# XMOS_power.net
KiCad netlist of a schematic drawn in Altium Designer
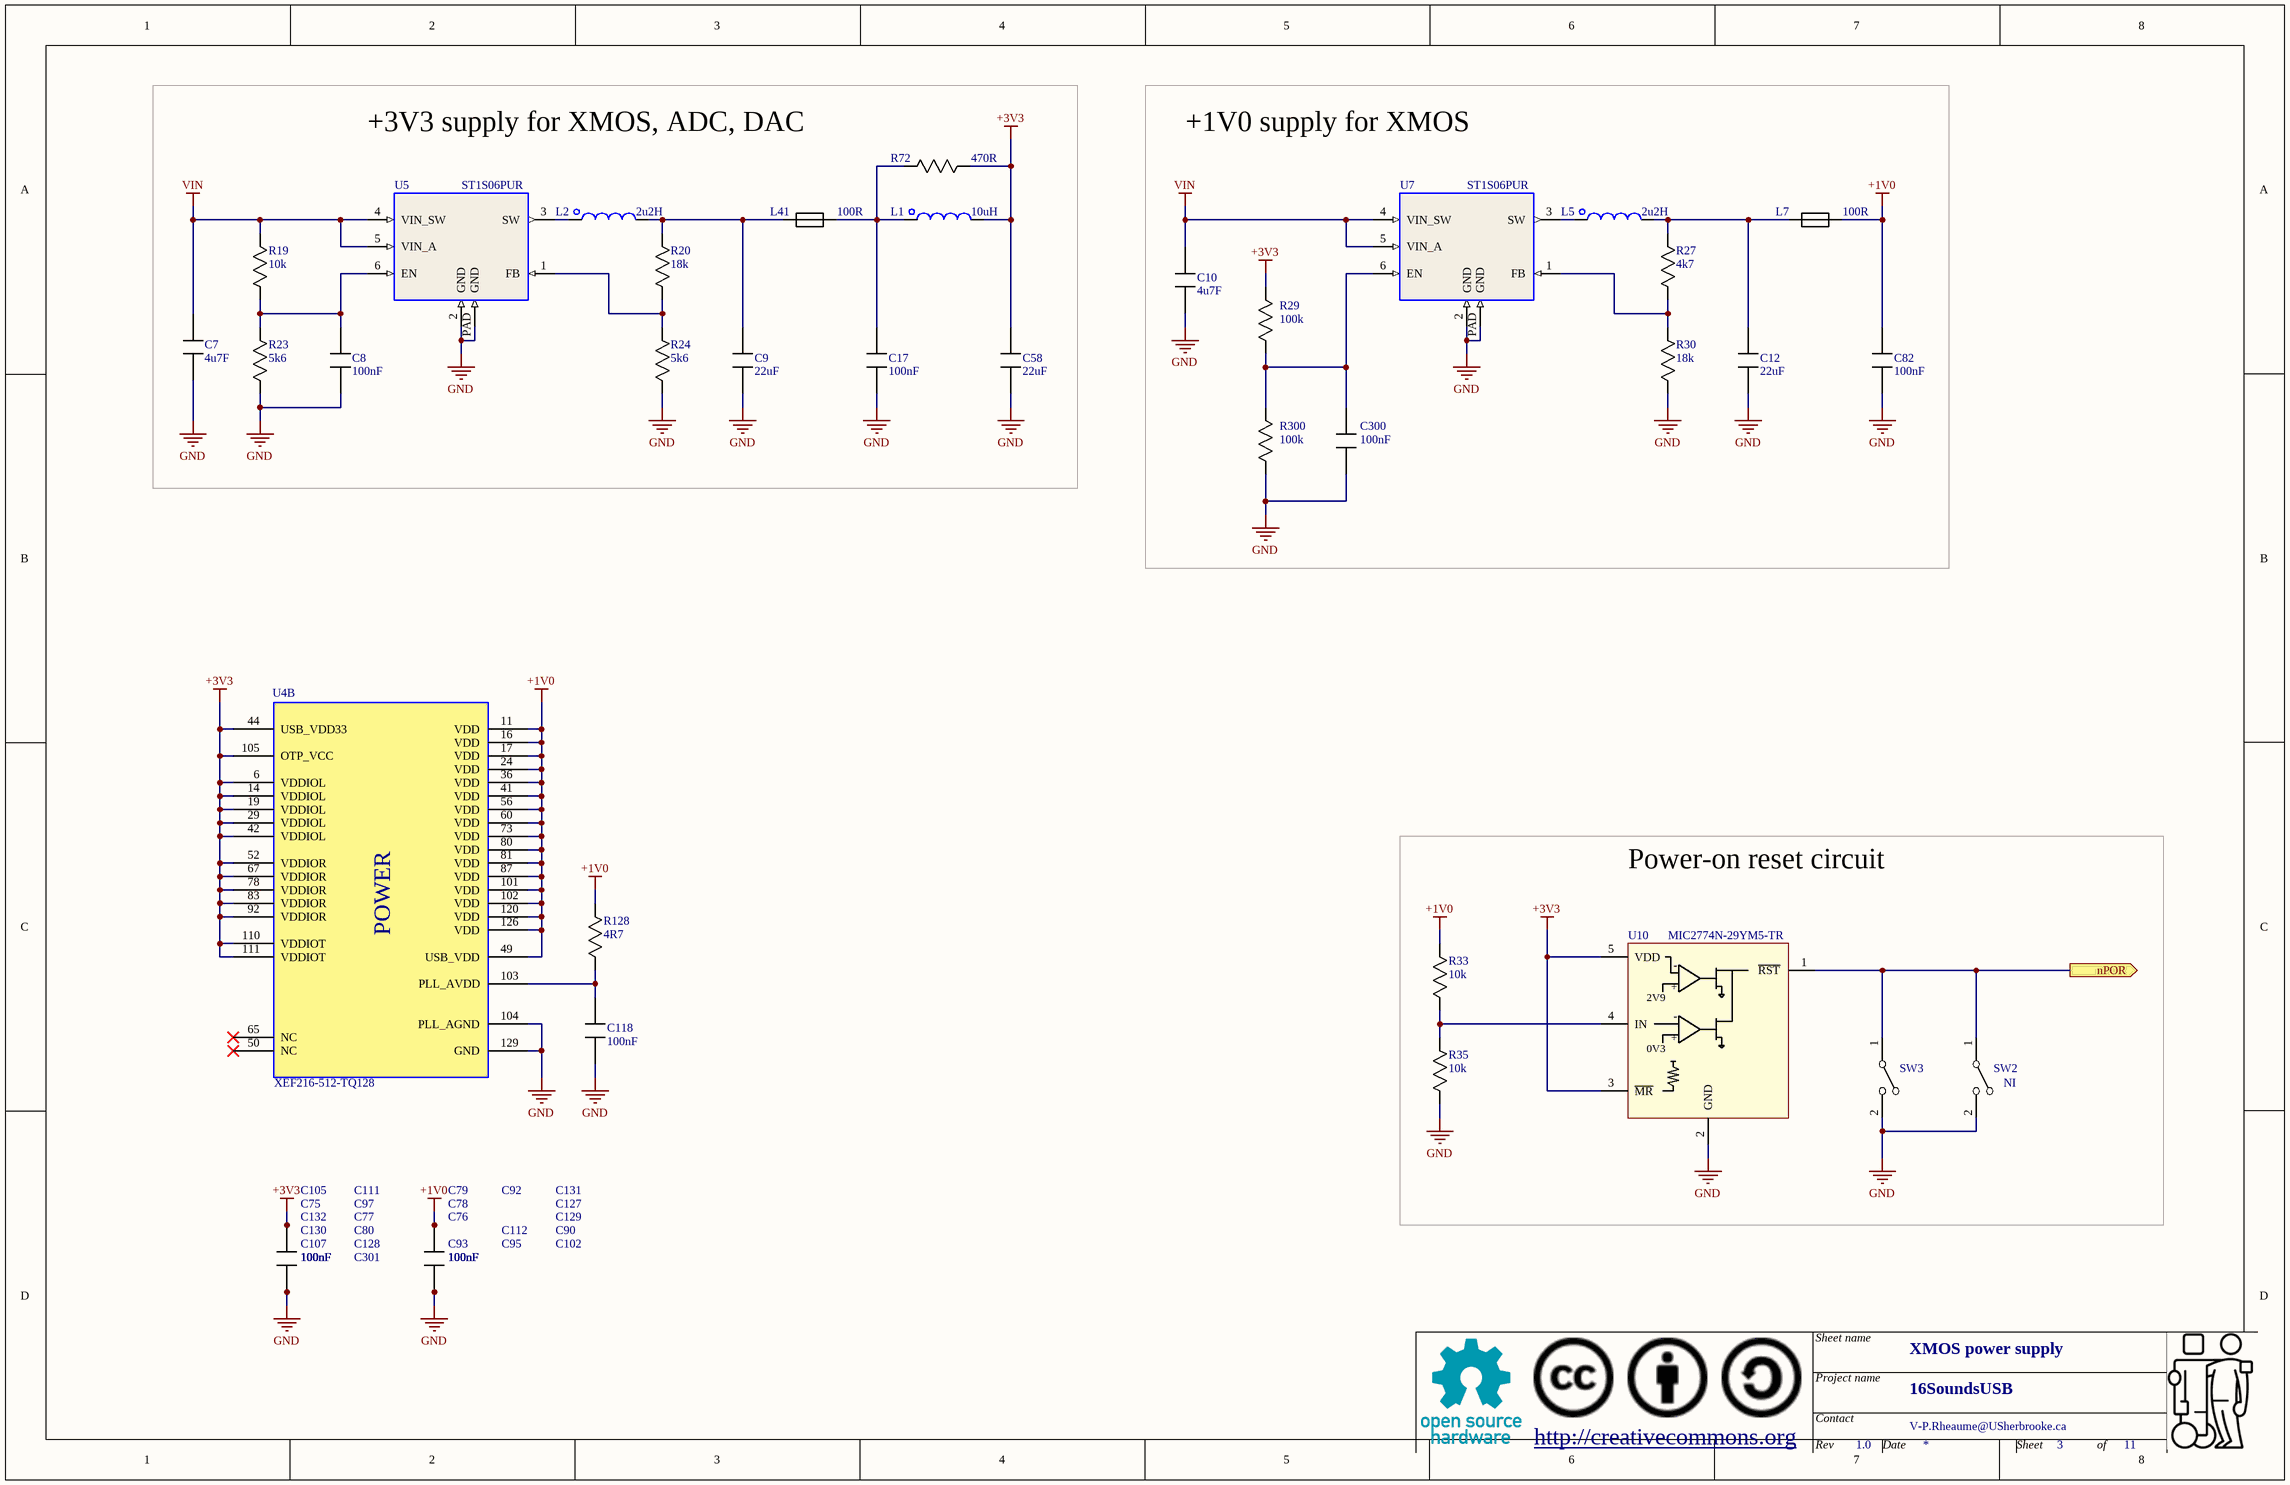
[diagram p0: XMOS_power.SchDoc]

(export (version "E")
  (design (tool "Eeschema 10.0.6"))
  (components
    (comp (ref "C7")
      (value "4u7F")
      (footprint "0805")
      (description "Capacitor")
      (fields (field (name "MFG") "Samsung"))
      (libsource (lib "INTER_2014") (part "Capacitor"))
    )
    (comp (ref "C8")
      (value "100nF")
      (footprint "0603")
      (description "Capacitor")
      (fields (field (name "MFG") "Samsung"))
      (libsource (lib "INTER_2014") (part "Capacitor"))
    )
    (comp (ref "C9")
      (value "22uF")
      (footprint "1206")
      (description "Capacitor")
      (fields (field (name "MFG") "Samsung"))
      (libsource (lib "INTER_2014") (part "Capacitor"))
    )
    (comp (ref "C10")
      (value "4u7F")
      (footprint "0805")
      (description "Capacitor")
      (fields (field (name "MFG") "Samsung"))
      (libsource (lib "INTER_2014") (part "Capacitor"))
    )
    (comp (ref "C12")
      (value "22uF")
      (footprint "1206")
      (description "Capacitor")
      (fields (field (name "MFG") "Samsung"))
      (libsource (lib "INTER_2014") (part "Capacitor"))
    )
    (comp (ref "C17")
      (value "100nF")
      (footprint "0603")
      (description "Capacitor")
      (fields (field (name "MFG") "Samsung"))
      (libsource (lib "INTER_2014") (part "Capacitor"))
    )
    (comp (ref "C58")
      (value "22uF")
      (footprint "1206")
      (description "Capacitor")
      (fields (field (name "MFG") "Samsung"))
      (libsource (lib "INTER_2014") (part "Capacitor"))
    )
    (comp (ref "C75")
      (value "100nF")
      (footprint "0603")
      (description "Capacitor")
      (fields (field (name "MFG") "Samsung"))
      (libsource (lib "INTER_2014") (part "Capacitor"))
    )
    (comp (ref "C76")
      (value "100nF")
      (footprint "0603")
      (description "Capacitor")
      (fields (field (name "MFG") "Samsung"))
      (libsource (lib "INTER_2014") (part "Capacitor"))
    )
    (comp (ref "C77")
      (value "100nF")
      (footprint "0603")
      (description "Capacitor")
      (fields (field (name "MFG") "Samsung"))
      (libsource (lib "INTER_2014") (part "Capacitor"))
    )
    (comp (ref "C78")
      (value "100nF")
      (footprint "0603")
      (description "Capacitor")
      (fields (field (name "MFG") "Samsung"))
      (libsource (lib "INTER_2014") (part "Capacitor"))
    )
    (comp (ref "C79")
      (value "100nF")
      (footprint "0603")
      (description "Capacitor")
      (fields (field (name "MFG") "Samsung"))
      (libsource (lib "INTER_2014") (part "Capacitor"))
    )
    (comp (ref "C80")
      (value "100nF")
      (footprint "0603")
      (description "Capacitor")
      (fields (field (name "MFG") "Samsung"))
      (libsource (lib "INTER_2014") (part "Capacitor"))
    )
    (comp (ref "C82")
      (value "100nF")
      (footprint "0603")
      (description "Capacitor")
      (fields (field (name "MFG") "Samsung"))
      (libsource (lib "INTER_2014") (part "Capacitor"))
    )
    (comp (ref "C90")
      (value "100nF")
      (footprint "0603")
      (description "Capacitor")
      (fields (field (name "MFG") "Samsung"))
      (libsource (lib "INTER_2014") (part "Capacitor"))
    )
    (comp (ref "C92")
      (value "100nF")
      (footprint "0603")
      (description "Capacitor")
      (fields (field (name "MFG") "Samsung"))
      (libsource (lib "INTER_2014") (part "Capacitor"))
    )
    (comp (ref "C93")
      (value "100nF")
      (footprint "0603")
      (description "Capacitor")
      (fields (field (name "MFG") "Samsung"))
      (libsource (lib "INTER_2014") (part "Capacitor"))
    )
    (comp (ref "C95")
      (value "100nF")
      (footprint "0603")
      (description "Capacitor")
      (fields (field (name "MFG") "Samsung"))
      (libsource (lib "INTER_2014") (part "Capacitor"))
    )
    (comp (ref "C97")
      (value "100nF")
      (footprint "0603")
      (description "Capacitor")
      (fields (field (name "MFG") "Samsung"))
      (libsource (lib "INTER_2014") (part "Capacitor"))
    )
    (comp (ref "C102")
      (value "100nF")
      (footprint "0603")
      (description "Capacitor")
      (fields (field (name "MFG") "Samsung"))
      (libsource (lib "INTER_2014") (part "Capacitor"))
    )
    (comp (ref "C105")
      (value "100nF")
      (footprint "0603")
      (description "Capacitor")
      (fields (field (name "MFG") "Samsung"))
      (libsource (lib "INTER_2014") (part "Capacitor"))
    )
    (comp (ref "C107")
      (value "100nF")
      (footprint "0603")
      (description "Capacitor")
      (fields (field (name "MFG") "Samsung"))
      (libsource (lib "INTER_2014") (part "Capacitor"))
    )
    (comp (ref "C111")
      (value "100nF")
      (footprint "0603")
      (description "Capacitor")
      (fields (field (name "MFG") "Samsung"))
      (libsource (lib "INTER_2014") (part "Capacitor"))
    )
    (comp (ref "C112")
      (value "100nF")
      (footprint "0603")
      (description "Capacitor")
      (fields (field (name "MFG") "Samsung"))
      (libsource (lib "INTER_2014") (part "Capacitor"))
    )
    (comp (ref "C118")
      (value "100nF")
      (footprint "0603")
      (description "Capacitor")
      (fields (field (name "MFG") "Samsung"))
      (libsource (lib "INTER_2014") (part "Capacitor"))
    )
    (comp (ref "C127")
      (value "100nF")
      (footprint "0603")
      (description "Capacitor")
      (fields (field (name "MFG") "Samsung"))
      (libsource (lib "INTER_2014") (part "Capacitor"))
    )
    (comp (ref "C128")
      (value "100nF")
      (footprint "0603")
      (description "Capacitor")
      (fields (field (name "MFG") "Samsung"))
      (libsource (lib "INTER_2014") (part "Capacitor"))
    )
    (comp (ref "C129")
      (value "100nF")
      (footprint "0603")
      (description "Capacitor")
      (fields (field (name "MFG") "Samsung"))
      (libsource (lib "INTER_2014") (part "Capacitor"))
    )
    (comp (ref "C130")
      (value "100nF")
      (footprint "0603")
      (description "Capacitor")
      (fields (field (name "MFG") "Samsung"))
      (libsource (lib "INTER_2014") (part "Capacitor"))
    )
    (comp (ref "C131")
      (value "100nF")
      (footprint "0603")
      (description "Capacitor")
      (fields (field (name "MFG") "Samsung"))
      (libsource (lib "INTER_2014") (part "Capacitor"))
    )
    (comp (ref "C132")
      (value "100nF")
      (footprint "0603")
      (description "Capacitor")
      (fields (field (name "MFG") "Samsung"))
      (libsource (lib "INTER_2014") (part "Capacitor"))
    )
    (comp (ref "C300")
      (value "100nF")
      (footprint "0603")
      (description "Capacitor")
      (fields (field (name "MFG") "Samsung"))
      (libsource (lib "INTER_2014") (part "Capacitor"))
    )
    (comp (ref "C301")
      (value "100nF")
      (footprint "0603")
      (description "Capacitor")
      (fields (field (name "MFG") "Samsung"))
      (libsource (lib "INTER_2014") (part "Capacitor"))
    )
    (comp (ref "L1")
      (value "10uH")
      (footprint "IND_252012CDMC/DS")
      (description "Inductor")
      (fields (field (name "MFG") "Murata"))
      (libsource (lib "INTER_2014") (part "Inductor"))
    )
    (comp (ref "L2")
      (value "2u2H")
      (footprint "IND_252012CDMC/DS")
      (description "Inductor")
      (fields (field (name "MFG") "Murata"))
      (libsource (lib "INTER_2014") (part "Inductor"))
    )
    (comp (ref "L5")
      (value "2u2H")
      (footprint "IND_252012CDMC/DS")
      (description "Inductor")
      (fields (field (name "MFG") "Murata"))
      (libsource (lib "INTER_2014") (part "Inductor"))
    )
    (comp (ref "L7")
      (value "100R")
      (footprint "0805")
      (description "Ferrite")
      (fields (field (name "MFG") "Bourns"))
      (libsource (lib "INTER_2014") (part "Ferrite"))
    )
    (comp (ref "L41")
      (value "100R")
      (footprint "0805")
      (description "Ferrite")
      (fields (field (name "MFG") "Bourns"))
      (libsource (lib "INTER_2014") (part "Ferrite"))
    )
    (comp (ref "R19")
      (value "10k")
      (footprint "0603")
      (description "Resistor")
      (fields (field (name "MFG") "Yageo"))
      (libsource (lib "INTER_2014") (part "Resistor"))
    )
    (comp (ref "R20")
      (value "18k")
      (footprint "0603")
      (description "Resistor")
      (fields (field (name "MFG") "Yageo"))
      (libsource (lib "INTER_2014") (part "Resistor"))
    )
    (comp (ref "R23")
      (value "5k6")
      (footprint "0603")
      (description "Resistor")
      (fields (field (name "MFG") "Yageo"))
      (libsource (lib "INTER_2014") (part "Resistor"))
    )
    (comp (ref "R24")
      (value "5k6")
      (footprint "0603")
      (description "Resistor")
      (fields (field (name "MFG") "Yageo"))
      (libsource (lib "INTER_2014") (part "Resistor"))
    )
    (comp (ref "R27")
      (value "4k7")
      (footprint "0603")
      (description "Resistor")
      (fields (field (name "MFG") "Yageo"))
      (libsource (lib "INTER_2014") (part "Resistor"))
    )
    (comp (ref "R29")
      (value "100k")
      (footprint "0603")
      (description "Resistor")
      (fields (field (name "MFG") "Yageo"))
      (libsource (lib "INTER_2014") (part "Resistor"))
    )
    (comp (ref "R30")
      (value "18k")
      (footprint "0603")
      (description "Resistor")
      (fields (field (name "MFG") "Yageo"))
      (libsource (lib "INTER_2014") (part "Resistor"))
    )
    (comp (ref "R33")
      (value "10k")
      (footprint "0603")
      (description "Resistor")
      (fields (field (name "MFG") "Yageo"))
      (libsource (lib "INTER_2014") (part "Resistor"))
    )
    (comp (ref "R35")
      (value "10k")
      (footprint "0603")
      (description "Resistor")
      (fields (field (name "MFG") "Yageo"))
      (libsource (lib "INTER_2014") (part "Resistor"))
    )
    (comp (ref "R72")
      (value "470R")
      (footprint "0603")
      (description "Resistor")
      (fields (field (name "MFG") "Yageo"))
      (libsource (lib "INTER_2014") (part "Resistor"))
    )
    (comp (ref "R128")
      (value "4R7")
      (footprint "0603")
      (description "Resistor")
      (fields (field (name "MFG") "Yageo"))
      (libsource (lib "INTER_2014") (part "Resistor"))
    )
    (comp (ref "R300")
      (value "100k")
      (footprint "0603")
      (description "Resistor")
      (fields (field (name "MFG") "Yageo"))
      (libsource (lib "INTER_2014") (part "Resistor"))
    )
    (comp (ref "SW2")
      (value "Button")
      (footprint "BUTTON_WS-TASV")
      (fields (field (name "MFG") "Wurth") (field (name "NI") "NI"))
      (libsource (lib "INTER_2014") (part "Button"))
    )
    (comp (ref "SW3")
      (value "Button")
      (footprint "BUTTON_WS-TASV")
      (fields (field (name "MFG") "Wurth"))
      (libsource (lib "INTER_2014") (part "Button"))
    )
    (comp (ref "U4")
      (value "~")
      (footprint "TQFP128_XMOS")
      (description "32-bit multicore microcontroller. 2 Tiles. 16 Logical Cores. 512KB SRAM. 1000MIPS. TQFP128.")
      (fields (field (name "MFG") "XMOS") (field (name "MFG_PN") "XEF216-512-TQ128"))
      (libsource (lib "INTER_2014") (part "XMOS_XEF216-512-TQ128"))
    )
    (comp (ref "U5")
      (value "ST1S06PUR")
      (footprint "DFN6_ST1S06")
      (description "DC-DC Buck Converter, 1.5A, 1.5MHz, DFN6")
      (fields (field (name "MFG") "ST Microelectronics") (field (name "MFG_PN") "ST1S06PUR"))
      (libsource (lib "INTER_2014") (part "ST1S06PUR"))
    )
    (comp (ref "U7")
      (value "ST1S06PUR")
      (footprint "DFN6_ST1S06")
      (description "DC-DC Buck Converter, 1.5A, 1.5MHz, DFN6")
      (fields (field (name "MFG") "ST Microelectronics") (field (name "MFG_PN") "ST1S06PUR"))
      (libsource (lib "INTER_2014") (part "ST1S06PUR"))
    )
    (comp (ref "U10")
      (value "MIC2774N-29YM5-TR")
      (footprint "SOT23_5")
      (description "Voltage supervisor and power-on timer, dual")
      (fields (field (name "MFG") "Micrel"))
      (libsource (lib "INTER_2014") (part "MIC2774N-29YM5-TR"))
    )
  )
  (nets
    (net (code "1") (name "+1V0") (class "Default")
      (node (ref "C102") (pin "1") (pintype "passive"))
      (node (ref "C112") (pin "1") (pintype "passive"))
      (node (ref "C127") (pin "1") (pintype "passive"))
      (node (ref "C129") (pin "1") (pintype "passive"))
      (node (ref "C131") (pin "1") (pintype "passive"))
      (node (ref "C76") (pin "1") (pintype "passive"))
      (node (ref "C78") (pin "1") (pintype "passive"))
      (node (ref "C79") (pin "1") (pintype "passive"))
      (node (ref "C82") (pin "1") (pintype "passive"))
      (node (ref "C90") (pin "1") (pintype "passive"))
      (node (ref "C92") (pin "1") (pintype "passive"))
      (node (ref "C93") (pin "1") (pintype "passive"))
      (node (ref "C95") (pin "1") (pintype "passive"))
      (node (ref "L7") (pin "2") (pintype "passive"))
      (node (ref "R128") (pin "1") (pintype "passive"))
      (node (ref "R33") (pin "1") (pintype "passive"))
      (node (ref "U4") (pin "101") (pinfunction "VDD_101") (pintype "power_in"))
      (node (ref "U4") (pin "102") (pinfunction "VDD_102") (pintype "power_in"))
      (node (ref "U4") (pin "11") (pinfunction "VDD_11") (pintype "power_in"))
      (node (ref "U4") (pin "120") (pinfunction "VDD_120") (pintype "power_in"))
      (node (ref "U4") (pin "126") (pinfunction "VDD_126") (pintype "power_in"))
      (node (ref "U4") (pin "16") (pinfunction "VDD_16") (pintype "power_in"))
      (node (ref "U4") (pin "17") (pinfunction "VDD_17") (pintype "power_in"))
      (node (ref "U4") (pin "24") (pinfunction "VDD_24") (pintype "power_in"))
      (node (ref "U4") (pin "36") (pinfunction "VDD_36") (pintype "power_in"))
      (node (ref "U4") (pin "41") (pinfunction "VDD_41") (pintype "power_in"))
      (node (ref "U4") (pin "49") (pinfunction "USB_VDD_49") (pintype "power_in"))
      (node (ref "U4") (pin "56") (pinfunction "VDD_56") (pintype "power_in"))
      (node (ref "U4") (pin "60") (pinfunction "VDD_60") (pintype "power_in"))
      (node (ref "U4") (pin "73") (pinfunction "VDD_73") (pintype "power_in"))
      (node (ref "U4") (pin "80") (pinfunction "VDD_80") (pintype "power_in"))
      (node (ref "U4") (pin "81") (pinfunction "VDD_81") (pintype "power_in"))
      (node (ref "U4") (pin "87") (pinfunction "VDD_87") (pintype "power_in"))
    )
    (net (code "2") (name "+3V3") (class "Default")
      (node (ref "C105") (pin "1") (pintype "passive"))
      (node (ref "C107") (pin "1") (pintype "passive"))
      (node (ref "C111") (pin "1") (pintype "passive"))
      (node (ref "C128") (pin "1") (pintype "passive"))
      (node (ref "C130") (pin "1") (pintype "passive"))
      (node (ref "C132") (pin "1") (pintype "passive"))
      (node (ref "C301") (pin "1") (pintype "passive"))
      (node (ref "C58") (pin "1") (pintype "passive"))
      (node (ref "C75") (pin "1") (pintype "passive"))
      (node (ref "C77") (pin "1") (pintype "passive"))
      (node (ref "C80") (pin "1") (pintype "passive"))
      (node (ref "C97") (pin "1") (pintype "passive"))
      (node (ref "L1") (pin "2") (pintype "passive"))
      (node (ref "R29") (pin "1") (pintype "passive"))
      (node (ref "R72") (pin "1") (pintype "passive"))
      (node (ref "U10") (pin "3") (pinfunction "~{MR}_3") (pintype "passive"))
      (node (ref "U10") (pin "5") (pinfunction "VDD_5") (pintype "passive"))
      (node (ref "U4") (pin "105") (pinfunction "OTP_VCC_105") (pintype "power_in"))
      (node (ref "U4") (pin "110") (pinfunction "VDDIOT_110") (pintype "power_in"))
      (node (ref "U4") (pin "111") (pinfunction "VDDIOT_111") (pintype "power_in"))
      (node (ref "U4") (pin "14") (pinfunction "VDDIOL_14") (pintype "power_in"))
      (node (ref "U4") (pin "19") (pinfunction "VDDIOL_19") (pintype "power_in"))
      (node (ref "U4") (pin "29") (pinfunction "VDDIOL_29") (pintype "power_in"))
      (node (ref "U4") (pin "42") (pinfunction "VDDIOL_42") (pintype "power_in"))
      (node (ref "U4") (pin "44") (pinfunction "USB_VDD33_44") (pintype "power_in"))
      (node (ref "U4") (pin "52") (pinfunction "VDDIOR_52") (pintype "power_in"))
      (node (ref "U4") (pin "6") (pinfunction "VDDIOL_6") (pintype "power_in"))
      (node (ref "U4") (pin "67") (pinfunction "VDDIOR_67") (pintype "power_in"))
      (node (ref "U4") (pin "78") (pinfunction "VDDIOR_78") (pintype "power_in"))
      (node (ref "U4") (pin "83") (pinfunction "VDDIOR_83") (pintype "power_in"))
      (node (ref "U4") (pin "92") (pinfunction "VDDIOR_92") (pintype "power_in"))
    )
    (net (code "3") (name "/nPOR") (class "Default")
      (node (ref "SW2") (pin "1") (pintype "passive"))
      (node (ref "SW3") (pin "1") (pintype "passive"))
      (node (ref "U10") (pin "1") (pinfunction "~{RST}_1") (pintype "open_collector"))
    )
    (net (code "4") (name "GND") (class "Default")
      (node (ref "C10") (pin "2") (pintype "passive"))
      (node (ref "C102") (pin "2") (pintype "passive"))
      (node (ref "C105") (pin "2") (pintype "passive"))
      (node (ref "C107") (pin "2") (pintype "passive"))
      (node (ref "C111") (pin "2") (pintype "passive"))
      (node (ref "C112") (pin "2") (pintype "passive"))
      (node (ref "C118") (pin "2") (pintype "passive"))
      (node (ref "C12") (pin "2") (pintype "passive"))
      (node (ref "C127") (pin "2") (pintype "passive"))
      (node (ref "C128") (pin "2") (pintype "passive"))
      (node (ref "C129") (pin "2") (pintype "passive"))
      (node (ref "C130") (pin "2") (pintype "passive"))
      (node (ref "C131") (pin "2") (pintype "passive"))
      (node (ref "C132") (pin "2") (pintype "passive"))
      (node (ref "C17") (pin "2") (pintype "passive"))
      (node (ref "C300") (pin "2") (pintype "passive"))
      (node (ref "C301") (pin "2") (pintype "passive"))
      (node (ref "C58") (pin "2") (pintype "passive"))
      (node (ref "C7") (pin "2") (pintype "passive"))
      (node (ref "C75") (pin "2") (pintype "passive"))
      (node (ref "C76") (pin "2") (pintype "passive"))
      (node (ref "C77") (pin "2") (pintype "passive"))
      (node (ref "C78") (pin "2") (pintype "passive"))
      (node (ref "C79") (pin "2") (pintype "passive"))
      (node (ref "C8") (pin "2") (pintype "passive"))
      (node (ref "C80") (pin "2") (pintype "passive"))
      (node (ref "C82") (pin "2") (pintype "passive"))
      (node (ref "C9") (pin "2") (pintype "passive"))
      (node (ref "C90") (pin "2") (pintype "passive"))
      (node (ref "C92") (pin "2") (pintype "passive"))
      (node (ref "C93") (pin "2") (pintype "passive"))
      (node (ref "C95") (pin "2") (pintype "passive"))
      (node (ref "C97") (pin "2") (pintype "passive"))
      (node (ref "R23") (pin "2") (pintype "passive"))
      (node (ref "R24") (pin "2") (pintype "passive"))
      (node (ref "R30") (pin "2") (pintype "passive"))
      (node (ref "R300") (pin "2") (pintype "passive"))
      (node (ref "R35") (pin "2") (pintype "passive"))
      (node (ref "SW2") (pin "2") (pintype "passive"))
      (node (ref "SW3") (pin "2") (pintype "passive"))
      (node (ref "U10") (pin "2") (pinfunction "GND_2") (pintype "passive"))
      (node (ref "U4") (pin "104") (pinfunction "PLL_AGND_104") (pintype "power_in"))
      (node (ref "U4") (pin "129") (pinfunction "GND_129") (pintype "power_in"))
      (node (ref "U5") (pin "2") (pinfunction "GND_2") (pintype "input"))
      (node (ref "U5") (pin "PAD") (pinfunction "GND_PAD") (pintype "input"))
      (node (ref "U7") (pin "2") (pinfunction "GND_2") (pintype "input"))
      (node (ref "U7") (pin "PAD") (pinfunction "GND_PAD") (pintype "input"))
    )
    (net (code "5") (name "Net-(C9-Pad1)") (class "Default")
      (node (ref "C9") (pin "1") (pintype "passive"))
      (node (ref "L2") (pin "2") (pintype "passive"))
      (node (ref "L41") (pin "1") (pintype "passive"))
      (node (ref "R20") (pin "1") (pintype "passive"))
    )
    (net (code "6") (name "Net-(C12-Pad1)") (class "Default")
      (node (ref "C12") (pin "1") (pintype "passive"))
      (node (ref "L5") (pin "2") (pintype "passive"))
      (node (ref "L7") (pin "1") (pintype "passive"))
      (node (ref "R27") (pin "1") (pintype "passive"))
    )
    (net (code "7") (name "Net-(C17-Pad1)") (class "Default")
      (node (ref "C17") (pin "1") (pintype "passive"))
      (node (ref "L1") (pin "1") (pintype "passive"))
      (node (ref "L41") (pin "2") (pintype "passive"))
      (node (ref "R72") (pin "2") (pintype "passive"))
    )
    (net (code "8") (name "Net-(U4B-PLL_AVDD)") (class "Default")
      (node (ref "C118") (pin "1") (pintype "passive"))
      (node (ref "R128") (pin "2") (pintype "passive"))
      (node (ref "U4") (pin "103") (pinfunction "PLL_AVDD_103") (pintype "power_in"))
    )
    (net (code "9") (name "Net-(U5-EN)") (class "Default")
      (node (ref "C8") (pin "1") (pintype "passive"))
      (node (ref "R19") (pin "2") (pintype "passive"))
      (node (ref "R23") (pin "1") (pintype "passive"))
      (node (ref "U5") (pin "6") (pinfunction "EN_6") (pintype "input"))
    )
    (net (code "10") (name "Net-(U5-FB)") (class "Default")
      (node (ref "R20") (pin "2") (pintype "passive"))
      (node (ref "R24") (pin "1") (pintype "passive"))
      (node (ref "U5") (pin "1") (pinfunction "FB_1") (pintype "input"))
    )
    (net (code "11") (name "Net-(U5-SW)") (class "Default")
      (node (ref "L2") (pin "1") (pintype "passive"))
      (node (ref "U5") (pin "3") (pinfunction "SW_3") (pintype "output"))
    )
    (net (code "12") (name "Net-(U7-EN)") (class "Default")
      (node (ref "C300") (pin "1") (pintype "passive"))
      (node (ref "R29") (pin "2") (pintype "passive"))
      (node (ref "R300") (pin "1") (pintype "passive"))
      (node (ref "U7") (pin "6") (pinfunction "EN_6") (pintype "input"))
    )
    (net (code "13") (name "Net-(U7-FB)") (class "Default")
      (node (ref "R27") (pin "2") (pintype "passive"))
      (node (ref "R30") (pin "1") (pintype "passive"))
      (node (ref "U7") (pin "1") (pinfunction "FB_1") (pintype "input"))
    )
    (net (code "14") (name "Net-(U7-SW)") (class "Default")
      (node (ref "L5") (pin "1") (pintype "passive"))
      (node (ref "U7") (pin "3") (pinfunction "SW_3") (pintype "output"))
    )
    (net (code "15") (name "Net-(U10-IN)") (class "Default")
      (node (ref "R33") (pin "2") (pintype "passive"))
      (node (ref "R35") (pin "1") (pintype "passive"))
      (node (ref "U10") (pin "4") (pinfunction "IN_4") (pintype "passive"))
    )
    (net (code "16") (name "VIN") (class "Default")
      (node (ref "C10") (pin "1") (pintype "passive"))
      (node (ref "C7") (pin "1") (pintype "passive"))
      (node (ref "R19") (pin "1") (pintype "passive"))
      (node (ref "U5") (pin "4") (pinfunction "VIN_SW_4") (pintype "input"))
      (node (ref "U5") (pin "5") (pinfunction "VIN_A_5") (pintype "input"))
      (node (ref "U7") (pin "4") (pinfunction "VIN_SW_4") (pintype "input"))
      (node (ref "U7") (pin "5") (pinfunction "VIN_A_5") (pintype "input"))
    )
    (net (code "17") (name "unconnected-(SW2-Pad3)") (class "Default")
      (node (ref "SW2") (pin "3") (pintype "passive"))
    )
    (net (code "18") (name "unconnected-(SW2-Pad4)") (class "Default")
      (node (ref "SW2") (pin "4") (pintype "passive"))
    )
    (net (code "19") (name "unconnected-(SW3-Pad3)") (class "Default")
      (node (ref "SW3") (pin "3") (pintype "passive"))
    )
    (net (code "20") (name "unconnected-(SW3-Pad4)") (class "Default")
      (node (ref "SW3") (pin "4") (pintype "passive"))
    )
    (net (code "21") (name "unconnected-(U4B-NC-Pad50)") (class "Default")
      (node (ref "U4") (pin "50") (pinfunction "NC_50") (pintype "passive+no_connect"))
    )
    (net (code "22") (name "unconnected-(U4B-NC-Pad65)") (class "Default")
      (node (ref "U4") (pin "65") (pinfunction "NC_65") (pintype "passive+no_connect"))
    )
  )
)
